# 3_MCU.net
KiCad netlist of a schematic drawn in Altium Designer
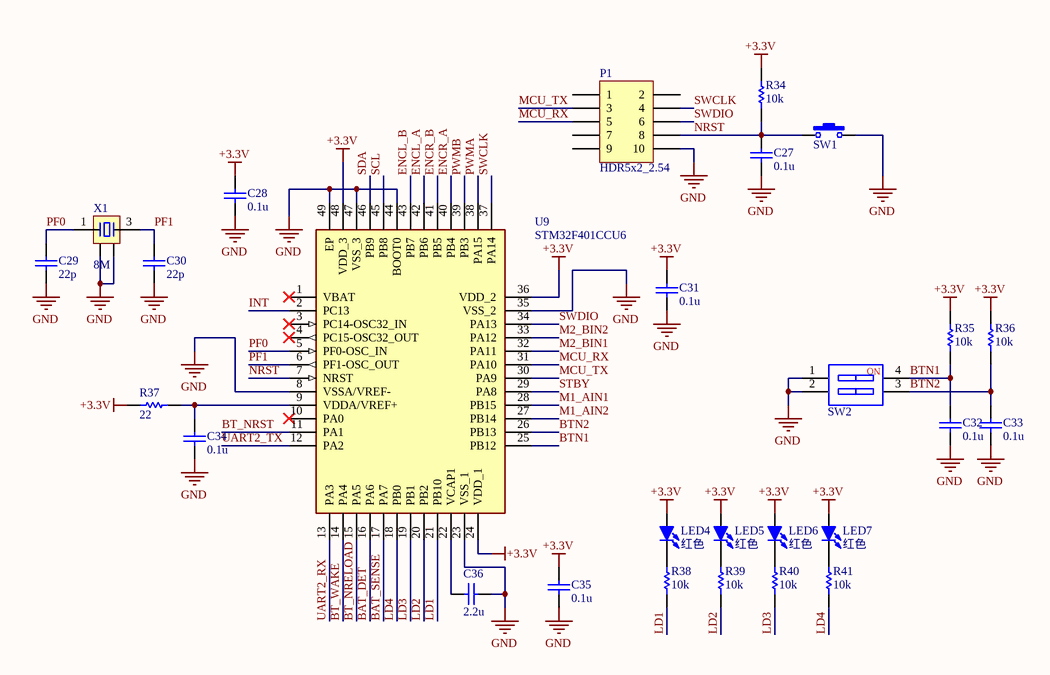
[diagram p0: 3_MCU.SchDoc]

(export (version "E")
  (design (tool "Eeschema 10.0.6"))
  (components
    (comp (ref "C27")
      (value "0.1u")
      (footprint "CAP_0603_SMD")
      (description "Capacitor, 0603, SMD")
      (fields (field (name "PUBLISHER") "Altium Limited"))
      (libsource (lib "myRLC") (part "CAP_0603_SMD"))
    )
    (comp (ref "C28")
      (value "0.1u")
      (footprint "CAP_0603_SMD")
      (description "Capacitor, 0603, SMD")
      (fields (field (name "PUBLISHER") "Altium Limited"))
      (libsource (lib "myRLC") (part "CAP_0603_SMD"))
    )
    (comp (ref "C29")
      (value "22p")
      (footprint "CAP_0603_SMD")
      (description "Capacitor, 0603, SMD")
      (fields (field (name "PUBLISHER") "Altium Limited"))
      (libsource (lib "myRLC") (part "CAP_0603_SMD"))
    )
    (comp (ref "C30")
      (value "22p")
      (footprint "CAP_0603_SMD")
      (description "Capacitor, 0603, SMD")
      (fields (field (name "PUBLISHER") "Altium Limited"))
      (libsource (lib "myRLC") (part "CAP_0603_SMD"))
    )
    (comp (ref "C31")
      (value "0.1u")
      (footprint "CAP_0603_SMD")
      (description "Capacitor, 0603, SMD")
      (fields (field (name "PUBLISHER") "Altium Limited"))
      (libsource (lib "myRLC") (part "CAP_0603_SMD"))
    )
    (comp (ref "C32")
      (value "0.1u")
      (footprint "CAP_0603_SMD")
      (description "Capacitor, 0603, SMD")
      (fields (field (name "PUBLISHER") "Altium Limited"))
      (libsource (lib "myRLC") (part "CAP_0603_SMD"))
    )
    (comp (ref "C33")
      (value "0.1u")
      (footprint "CAP_0603_SMD")
      (description "Capacitor, 0603, SMD")
      (fields (field (name "PUBLISHER") "Altium Limited"))
      (libsource (lib "myRLC") (part "CAP_0603_SMD"))
    )
    (comp (ref "C34")
      (value "0.1u")
      (footprint "CAP_0603_SMD")
      (description "Capacitor, 0603, SMD")
      (fields (field (name "PUBLISHER") "Altium Limited"))
      (libsource (lib "myRLC") (part "CAP_0603_SMD"))
    )
    (comp (ref "C35")
      (value "0.1u")
      (footprint "CAP_0603_SMD")
      (description "Capacitor, 0603, SMD")
      (fields (field (name "PUBLISHER") "Altium Limited"))
      (libsource (lib "myRLC") (part "CAP_0603_SMD"))
    )
    (comp (ref "C36")
      (value "2.2u")
      (footprint "CAP_0603_SMD")
      (description "Capacitor, 0603, SMD")
      (fields (field (name "PUBLISHER") "Altium Limited"))
      (libsource (lib "myRLC") (part "CAP_0603_SMD"))
    )
    (comp (ref "LED4")
      (value "红色")
      (footprint "LED0603_Y")
      (description "贴片LED")
      (libsource (lib "0.3 - LED发光二极管") (part "LED-SMD"))
    )
    (comp (ref "LED5")
      (value "红色")
      (footprint "LED0603_Y")
      (description "贴片LED")
      (libsource (lib "0.3 - LED发光二极管") (part "LED-SMD"))
    )
    (comp (ref "LED6")
      (value "红色")
      (footprint "LED0603_Y")
      (description "贴片LED")
      (libsource (lib "0.3 - LED发光二极管") (part "LED-SMD"))
    )
    (comp (ref "LED7")
      (value "红色")
      (footprint "LED0603_Y")
      (description "贴片LED")
      (libsource (lib "0.3 - LED发光二极管") (part "LED-SMD"))
    )
    (comp (ref "P1")
      (value "HDR5x2_2.54")
      (footprint "HDR5x2_2.54")
      (description "Header, 10-Pin, 2-Row")
      (fields (field (name "PUBLISHER") "Altium Limited"))
      (libsource (lib "myConnectors") (part "HDR5x2_2.54"))
    )
    (comp (ref "R34")
      (value "10k")
      (footprint "RES_0603_SMD")
      (description "Resistor, 0603, SMD")
      (fields (field (name "PUBLISHER") "Altium Limited"))
      (libsource (lib "myRLC") (part "RES_0603_SMD"))
    )
    (comp (ref "R35")
      (value "10k")
      (footprint "RES_0603_SMD")
      (description "Resistor, 0603, SMD")
      (fields (field (name "PUBLISHER") "Altium Limited"))
      (libsource (lib "myRLC") (part "RES_0603_SMD"))
    )
    (comp (ref "R36")
      (value "10k")
      (footprint "RES_0603_SMD")
      (description "Resistor, 0603, SMD")
      (fields (field (name "PUBLISHER") "Altium Limited"))
      (libsource (lib "myRLC") (part "RES_0603_SMD"))
    )
    (comp (ref "R37")
      (value "22")
      (footprint "RES_0603_SMD")
      (description "Resistor, 0603, SMD")
      (fields (field (name "PUBLISHER") "Altium Limited"))
      (libsource (lib "myRLC") (part "RES_0603_SMD"))
    )
    (comp (ref "R38")
      (value "10k")
      (footprint "RES_0603_SMD")
      (description "Resistor, 0603, SMD")
      (fields (field (name "PUBLISHER") "Altium Limited"))
      (libsource (lib "myRLC") (part "RES_0603_SMD"))
    )
    (comp (ref "R39")
      (value "10k")
      (footprint "RES_0603_SMD")
      (description "Resistor, 0603, SMD")
      (fields (field (name "PUBLISHER") "Altium Limited"))
      (libsource (lib "myRLC") (part "RES_0603_SMD"))
    )
    (comp (ref "R40")
      (value "10k")
      (footprint "RES_0603_SMD")
      (description "Resistor, 0603, SMD")
      (fields (field (name "PUBLISHER") "Altium Limited"))
      (libsource (lib "myRLC") (part "RES_0603_SMD"))
    )
    (comp (ref "R41")
      (value "10k")
      (footprint "RES_0603_SMD")
      (description "Resistor, 0603, SMD")
      (fields (field (name "PUBLISHER") "Altium Limited"))
      (libsource (lib "myRLC") (part "RES_0603_SMD"))
    )
    (comp (ref "SW1")
      (value "3x6x5")
      (footprint "SW SMD-3*6*4.3")
      (description "微动开关")
      (libsource (lib "0.7 - 常用按键-开关-蜂鸣器-电池-测试点") (part "SW-PB"))
    )
    (comp (ref "SW2")
      (value "SW-2P")
      (footprint "SW1.27 SMD-2P")
      (description "2路编码开关")
      (libsource (lib "0.7 - 常用按键-开关-蜂鸣器-电池-测试点") (part "SW-2P"))
    )
    (comp (ref "U9")
      (value "STM32F401CCU6")
      (footprint "TKY:QFN50P700X700X60-49N-D")
      (description "Integrated Circuit")
      (fields (field (name "MOUSER PART NUMBER") "511-STM32F401CCU6"))
      (libsource (lib "TKY") (part "STM32F401CCU6"))
    )
    (comp (ref "X1")
      (value "8M")
      (footprint "OSC 3225-4P")
      (description "4脚无源晶振")
      (libsource (lib "0.5 - 保险丝-晶振-光耦") (part "XTAL-4P"))
    )
  )
  (nets
    (net (code "1") (name "+3.3V") (class "Default")
      (node (ref "C28") (pin "1") (pinfunction "1_1") (pintype "passive"))
      (node (ref "C31") (pin "1") (pinfunction "1_1") (pintype "passive"))
      (node (ref "C35") (pin "1") (pinfunction "1_1") (pintype "passive"))
      (node (ref "LED4") (pin "1") (pinfunction "A_1") (pintype "passive"))
      (node (ref "LED5") (pin "1") (pinfunction "A_1") (pintype "passive"))
      (node (ref "LED6") (pin "1") (pinfunction "A_1") (pintype "passive"))
      (node (ref "LED7") (pin "1") (pinfunction "A_1") (pintype "passive"))
      (node (ref "R34") (pin "2") (pinfunction "2_2") (pintype "passive"))
      (node (ref "R35") (pin "1") (pinfunction "1_1") (pintype "passive"))
      (node (ref "R36") (pin "1") (pinfunction "1_1") (pintype "passive"))
      (node (ref "R37") (pin "2") (pinfunction "2_2") (pintype "passive"))
      (node (ref "U9") (pin "24") (pinfunction "VDD_1_24") (pintype "power_in"))
      (node (ref "U9") (pin "36") (pinfunction "VDD_2_36") (pintype "power_in"))
      (node (ref "U9") (pin "48") (pinfunction "VDD_3_48") (pintype "power_in"))
    )
    (net (code "2") (name "/BAT_DET") (class "Default")
      (node (ref "U9") (pin "16") (pinfunction "PA6_16") (pintype "passive"))
    )
    (net (code "3") (name "/BAT_SENSE") (class "Default")
      (node (ref "U9") (pin "17") (pinfunction "PA7_17") (pintype "passive"))
    )
    (net (code "4") (name "/BTN1") (class "Default")
      (node (ref "C32") (pin "2") (pinfunction "2_2") (pintype "passive"))
      (node (ref "R35") (pin "2") (pinfunction "2_2") (pintype "passive"))
      (node (ref "SW2") (pin "4") (pinfunction "4_4") (pintype "passive"))
      (node (ref "U9") (pin "25") (pinfunction "PB12_25") (pintype "passive"))
    )
    (net (code "5") (name "/BTN2") (class "Default")
      (node (ref "C33") (pin "2") (pinfunction "2_2") (pintype "passive"))
      (node (ref "R36") (pin "2") (pinfunction "2_2") (pintype "passive"))
      (node (ref "SW2") (pin "3") (pinfunction "3_3") (pintype "passive"))
      (node (ref "U9") (pin "26") (pinfunction "PB13_26") (pintype "passive"))
    )
    (net (code "6") (name "/BT_NRELOAD") (class "Default")
      (node (ref "U9") (pin "15") (pinfunction "PA5_15") (pintype "passive"))
    )
    (net (code "7") (name "/BT_NRST") (class "Default")
      (node (ref "U9") (pin "11") (pinfunction "PA1_11") (pintype "passive"))
    )
    (net (code "8") (name "/BT_WAKE") (class "Default")
      (node (ref "U9") (pin "14") (pinfunction "PA4_14") (pintype "passive"))
    )
    (net (code "9") (name "/ENCL_A") (class "Default")
      (node (ref "U9") (pin "42") (pinfunction "PB6_42") (pintype "passive"))
    )
    (net (code "10") (name "/ENCL_B") (class "Default")
      (node (ref "U9") (pin "43") (pinfunction "PB7_43") (pintype "passive"))
    )
    (net (code "11") (name "/ENCR_A") (class "Default")
      (node (ref "U9") (pin "40") (pinfunction "PB4_40") (pintype "passive"))
    )
    (net (code "12") (name "/ENCR_B") (class "Default")
      (node (ref "U9") (pin "41") (pinfunction "PB5_41") (pintype "passive"))
    )
    (net (code "13") (name "/INT") (class "Default")
      (node (ref "U9") (pin "2") (pinfunction "PC13_2") (pintype "passive"))
    )
    (net (code "14") (name "/LD1") (class "Default")
      (node (ref "R38") (pin "2") (pinfunction "2_2") (pintype "passive"))
      (node (ref "U9") (pin "21") (pinfunction "PB10_21") (pintype "passive"))
    )
    (net (code "15") (name "/LD2") (class "Default")
      (node (ref "R39") (pin "2") (pinfunction "2_2") (pintype "passive"))
      (node (ref "U9") (pin "20") (pinfunction "PB2_20") (pintype "passive"))
    )
    (net (code "16") (name "/LD3") (class "Default")
      (node (ref "R40") (pin "2") (pinfunction "2_2") (pintype "passive"))
      (node (ref "U9") (pin "19") (pinfunction "PB1_19") (pintype "passive"))
    )
    (net (code "17") (name "/LD4") (class "Default")
      (node (ref "R41") (pin "2") (pinfunction "2_2") (pintype "passive"))
      (node (ref "U9") (pin "18") (pinfunction "PB0_18") (pintype "passive"))
    )
    (net (code "18") (name "/M1_AIN1") (class "Default")
      (node (ref "U9") (pin "28") (pinfunction "PB15_28") (pintype "passive"))
    )
    (net (code "19") (name "/M1_AIN2") (class "Default")
      (node (ref "U9") (pin "27") (pinfunction "PB14_27") (pintype "passive"))
    )
    (net (code "20") (name "/M2_BIN1") (class "Default")
      (node (ref "U9") (pin "32") (pinfunction "PA11_32") (pintype "passive"))
    )
    (net (code "21") (name "/M2_BIN2") (class "Default")
      (node (ref "U9") (pin "33") (pinfunction "PA12_33") (pintype "passive"))
    )
    (net (code "22") (name "/MCU_RX") (class "Default")
      (node (ref "P1") (pin "5") (pinfunction "5_5") (pintype "passive"))
      (node (ref "U9") (pin "31") (pinfunction "PA10_31") (pintype "passive"))
    )
    (net (code "23") (name "/MCU_TX") (class "Default")
      (node (ref "P1") (pin "3") (pinfunction "3_3") (pintype "passive"))
      (node (ref "U9") (pin "30") (pinfunction "PA9_30") (pintype "passive"))
    )
    (net (code "24") (name "/NRST") (class "Default")
      (node (ref "C27") (pin "2") (pinfunction "2_2") (pintype "passive"))
      (node (ref "P1") (pin "8") (pinfunction "8_8") (pintype "passive"))
      (node (ref "R34") (pin "1") (pinfunction "1_1") (pintype "passive"))
      (node (ref "SW1") (pin "1") (pinfunction "1_1") (pintype "passive"))
      (node (ref "U9") (pin "7") (pinfunction "NRST_7") (pintype "input"))
    )
    (net (code "25") (name "/PF0") (class "Default")
      (node (ref "C29") (pin "1") (pinfunction "1_1") (pintype "passive"))
      (node (ref "U9") (pin "5") (pinfunction "PF0-OSC_IN_5") (pintype "input"))
      (node (ref "X1") (pin "1") (pinfunction "1_1") (pintype "passive"))
    )
    (net (code "26") (name "/PF1") (class "Default")
      (node (ref "C30") (pin "1") (pinfunction "1_1") (pintype "passive"))
      (node (ref "U9") (pin "6") (pinfunction "PF1-OSC_OUT_6") (pintype "output"))
      (node (ref "X1") (pin "3") (pinfunction "3_3") (pintype "passive"))
    )
    (net (code "27") (name "/PWMA") (class "Default")
      (node (ref "U9") (pin "38") (pinfunction "PA15_38") (pintype "passive"))
    )
    (net (code "28") (name "/PWMB") (class "Default")
      (node (ref "U9") (pin "39") (pinfunction "PB3_39") (pintype "passive"))
    )
    (net (code "29") (name "/SCL") (class "Default")
      (node (ref "U9") (pin "45") (pinfunction "PB8_45") (pintype "passive"))
    )
    (net (code "30") (name "/SDA") (class "Default")
      (node (ref "U9") (pin "46") (pinfunction "PB9_46") (pintype "passive"))
    )
    (net (code "31") (name "/STBY") (class "Default")
      (node (ref "U9") (pin "29") (pinfunction "PA8_29") (pintype "passive"))
    )
    (net (code "32") (name "/SWCLK") (class "Default")
      (node (ref "P1") (pin "4") (pinfunction "4_4") (pintype "passive"))
      (node (ref "U9") (pin "37") (pinfunction "PA14_37") (pintype "passive"))
    )
    (net (code "33") (name "/SWDIO") (class "Default")
      (node (ref "P1") (pin "6") (pinfunction "6_6") (pintype "passive"))
      (node (ref "U9") (pin "34") (pinfunction "PA13_34") (pintype "passive"))
    )
    (net (code "34") (name "/UART2_RX") (class "Default")
      (node (ref "U9") (pin "13") (pinfunction "PA3_13") (pintype "passive"))
    )
    (net (code "35") (name "/UART2_TX") (class "Default")
      (node (ref "U9") (pin "12") (pinfunction "PA2_12") (pintype "passive"))
    )
    (net (code "36") (name "GND") (class "Default")
      (node (ref "C27") (pin "1") (pinfunction "1_1") (pintype "passive"))
      (node (ref "C28") (pin "2") (pinfunction "2_2") (pintype "passive"))
      (node (ref "C29") (pin "2") (pinfunction "2_2") (pintype "passive"))
      (node (ref "C30") (pin "2") (pinfunction "2_2") (pintype "passive"))
      (node (ref "C31") (pin "2") (pinfunction "2_2") (pintype "passive"))
      (node (ref "C32") (pin "1") (pinfunction "1_1") (pintype "passive"))
      (node (ref "C33") (pin "1") (pinfunction "1_1") (pintype "passive"))
      (node (ref "C34") (pin "2") (pinfunction "2_2") (pintype "passive"))
      (node (ref "C35") (pin "2") (pinfunction "2_2") (pintype "passive"))
      (node (ref "C36") (pin "1") (pinfunction "1_1") (pintype "passive"))
      (node (ref "P1") (pin "10") (pinfunction "10_10") (pintype "passive"))
      (node (ref "SW1") (pin "2") (pinfunction "2_2") (pintype "passive"))
      (node (ref "SW2") (pin "1") (pinfunction "1_1") (pintype "passive"))
      (node (ref "SW2") (pin "2") (pinfunction "2_2") (pintype "passive"))
      (node (ref "U9") (pin "23") (pinfunction "VSS_1_23") (pintype "power_in"))
      (node (ref "U9") (pin "35") (pinfunction "VSS_2_35") (pintype "power_in"))
      (node (ref "U9") (pin "44") (pinfunction "BOOT0_44") (pintype "passive"))
      (node (ref "U9") (pin "47") (pinfunction "VSS_3_47") (pintype "power_in"))
      (node (ref "U9") (pin "49") (pinfunction "EP_49") (pintype "passive"))
      (node (ref "U9") (pin "8") (pinfunction "VSSA/VREF-_8") (pintype "power_in"))
      (node (ref "X1") (pin "2") (pinfunction "2_2") (pintype "passive"))
      (node (ref "X1") (pin "4") (pinfunction "4_4") (pintype "passive"))
    )
    (net (code "37") (name "Net-(LED4-K)") (class "Default")
      (node (ref "LED4") (pin "2") (pinfunction "K_2") (pintype "passive"))
      (node (ref "R38") (pin "1") (pinfunction "1_1") (pintype "passive"))
    )
    (net (code "38") (name "Net-(LED5-K)") (class "Default")
      (node (ref "LED5") (pin "2") (pinfunction "K_2") (pintype "passive"))
      (node (ref "R39") (pin "1") (pinfunction "1_1") (pintype "passive"))
    )
    (net (code "39") (name "Net-(LED6-K)") (class "Default")
      (node (ref "LED6") (pin "2") (pinfunction "K_2") (pintype "passive"))
      (node (ref "R40") (pin "1") (pinfunction "1_1") (pintype "passive"))
    )
    (net (code "40") (name "Net-(LED7-K)") (class "Default")
      (node (ref "LED7") (pin "2") (pinfunction "K_2") (pintype "passive"))
      (node (ref "R41") (pin "1") (pinfunction "1_1") (pintype "passive"))
    )
    (net (code "41") (name "Net-(U9-VCAP1)") (class "Default")
      (node (ref "C36") (pin "2") (pinfunction "2_2") (pintype "passive"))
      (node (ref "U9") (pin "22") (pinfunction "VCAP1_22") (pintype "passive"))
    )
    (net (code "42") (name "Net-(U9-VDDA{slash}VREF+)") (class "Default")
      (node (ref "C34") (pin "1") (pinfunction "1_1") (pintype "passive"))
      (node (ref "R37") (pin "1") (pinfunction "1_1") (pintype "passive"))
      (node (ref "U9") (pin "9") (pinfunction "VDDA/VREF+_9") (pintype "power_in"))
    )
    (net (code "43") (name "unconnected-(P1-Pad1)") (class "Default")
      (node (ref "P1") (pin "1") (pinfunction "1_1") (pintype "passive"))
    )
    (net (code "44") (name "unconnected-(P1-Pad2)") (class "Default")
      (node (ref "P1") (pin "2") (pinfunction "2_2") (pintype "passive"))
    )
    (net (code "45") (name "unconnected-(P1-Pad7)") (class "Default")
      (node (ref "P1") (pin "7") (pinfunction "7_7") (pintype "passive"))
    )
    (net (code "46") (name "unconnected-(P1-Pad9)") (class "Default")
      (node (ref "P1") (pin "9") (pinfunction "9_9") (pintype "passive"))
    )
    (net (code "47") (name "unconnected-(U9-PA0-Pad10)") (class "Default")
      (node (ref "U9") (pin "10") (pinfunction "PA0_10") (pintype "passive+no_connect"))
    )
    (net (code "48") (name "unconnected-(U9-PC14-OSC32_IN-Pad3)") (class "Default")
      (node (ref "U9") (pin "3") (pinfunction "PC14-OSC32_IN_3") (pintype "input+no_connect"))
    )
    (net (code "49") (name "unconnected-(U9-PC15-OSC32_OUT-Pad4)") (class "Default")
      (node (ref "U9") (pin "4") (pinfunction "PC15-OSC32_OUT_4") (pintype "output+no_connect"))
    )
    (net (code "50") (name "unconnected-(U9-VBAT-Pad1)") (class "Default")
      (node (ref "U9") (pin "1") (pinfunction "VBAT_1") (pintype "passive+no_connect"))
    )
  )
)
